# BlinkyBoard.net
KiCad netlist of a schematic drawn in EAGLE
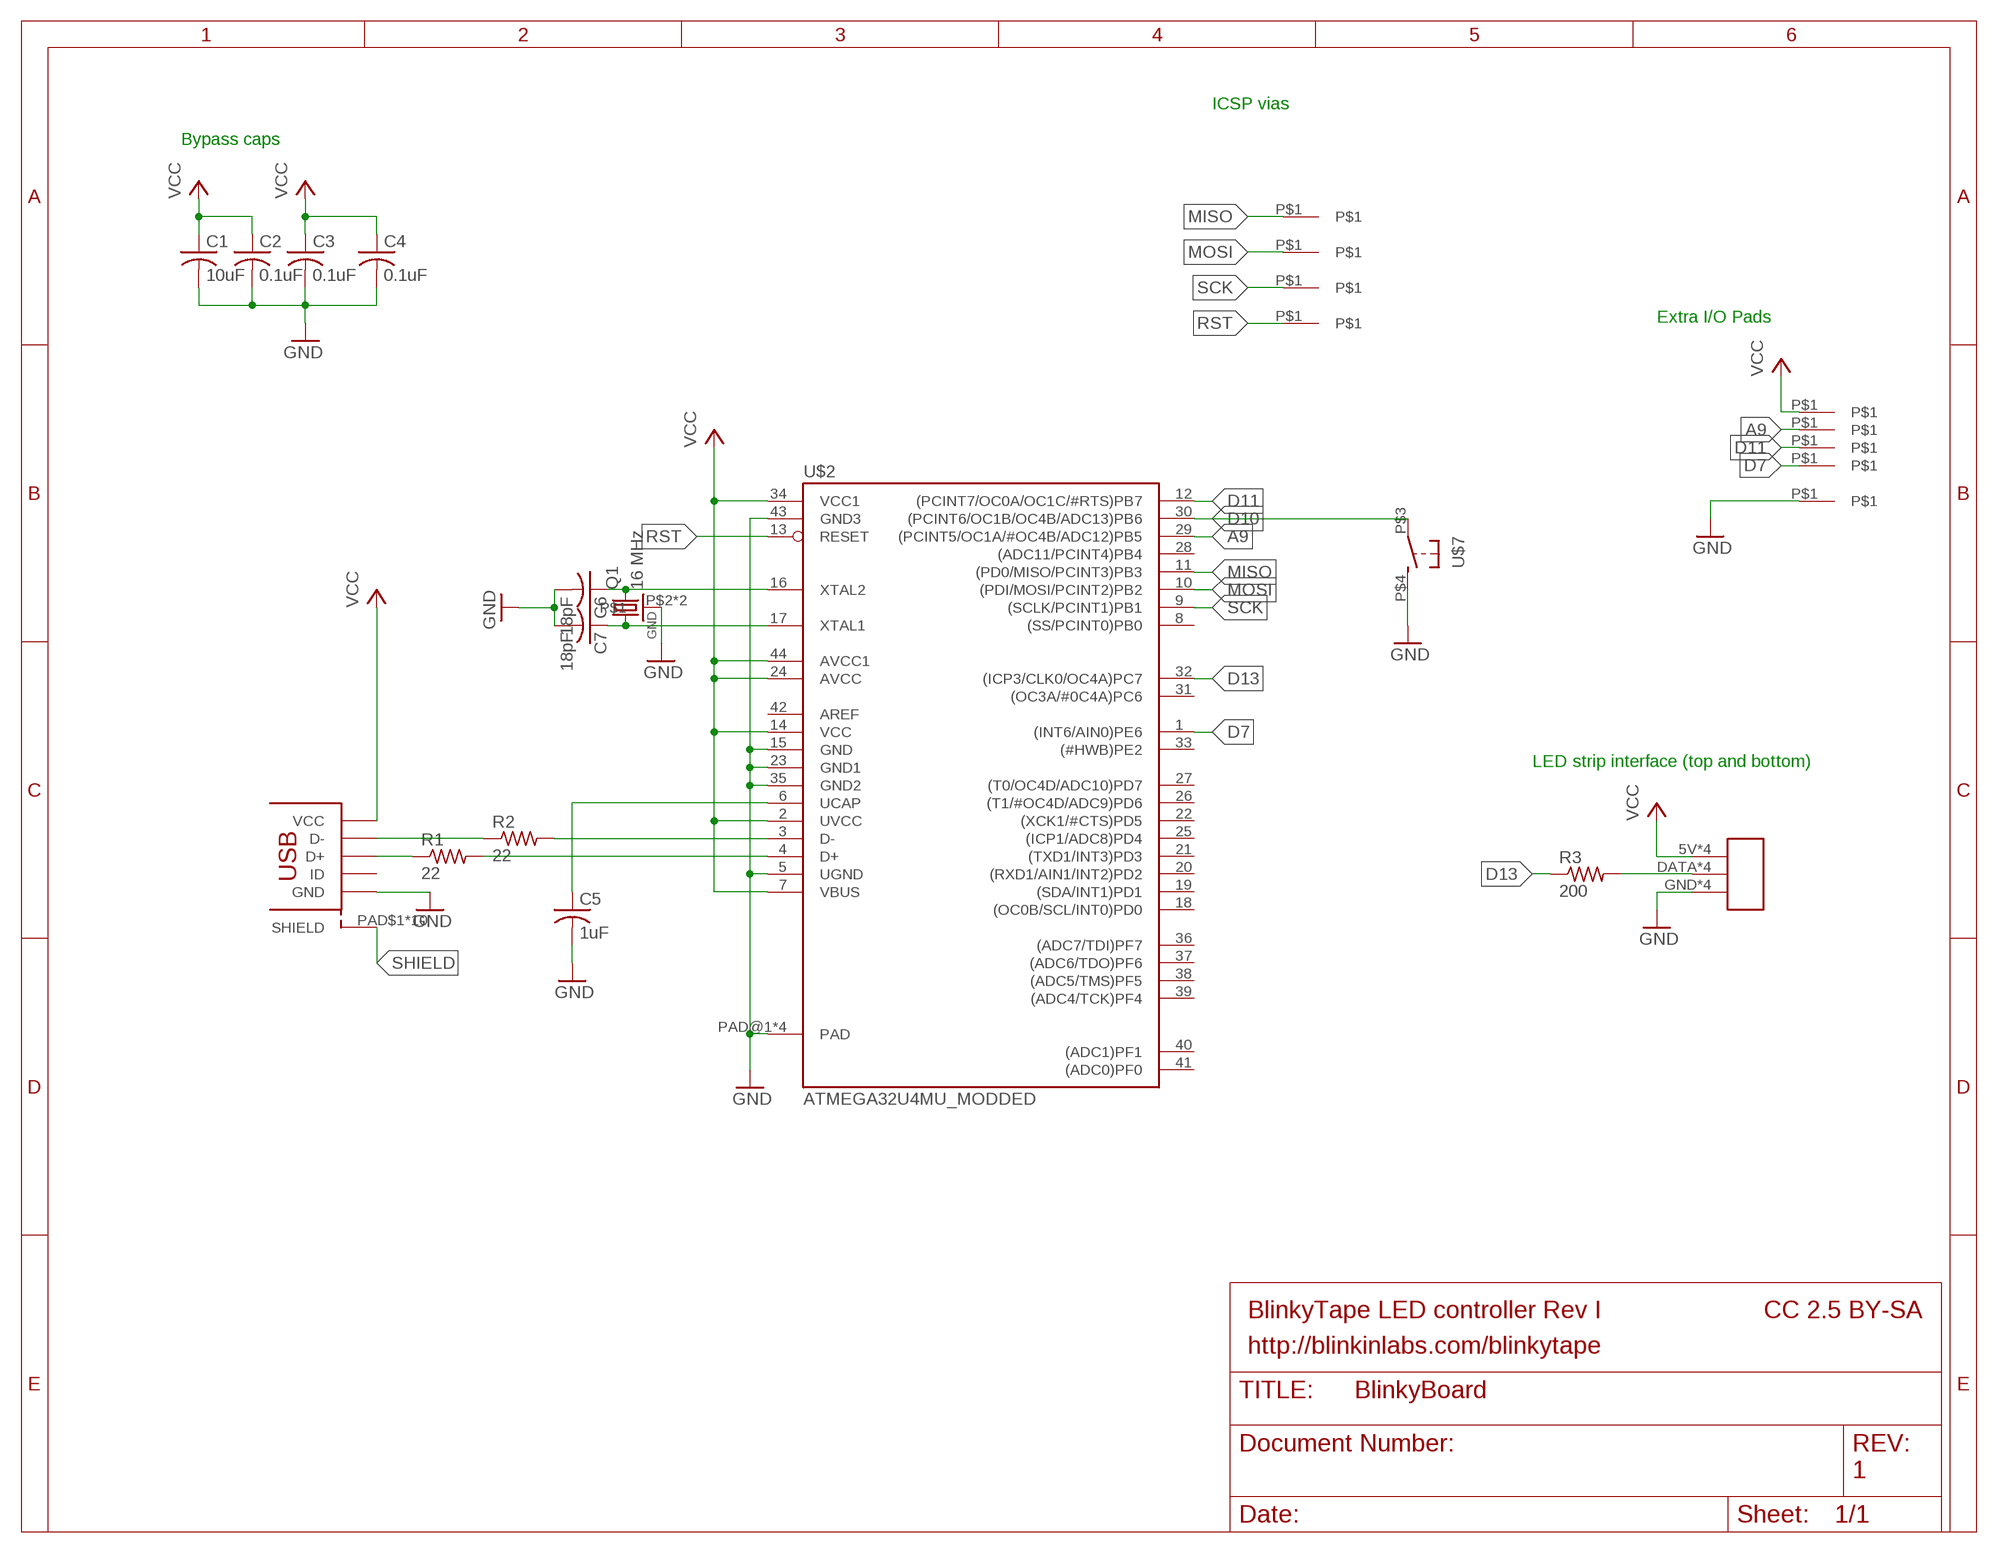
[diagram p0: schematic, sheet 1]

(export (version "E")
  (design (tool "Eeschema 10.0.6"))
  (components
    (comp (ref "C1")
      (value "10uF")
      (footprint "eagle-import:C0603K")
      (libsource (lib "eagle-import") (part "C-USC0603K"))
    )
    (comp (ref "C2")
      (value "0.1uF")
      (footprint "eagle-import:CAP_0402_KEMET_MEDIAN")
      (libsource (lib "eagle-import") (part "C_US"))
    )
    (comp (ref "C3")
      (value "0.1uF")
      (footprint "eagle-import:CAP_0402_KEMET_MEDIAN")
      (libsource (lib "eagle-import") (part "C_US"))
    )
    (comp (ref "C4")
      (value "0.1uF")
      (footprint "eagle-import:CAP_0402_KEMET_MEDIAN")
      (libsource (lib "eagle-import") (part "C_US"))
    )
    (comp (ref "C5")
      (value "1uF")
      (footprint "eagle-import:CAP_0402_KEMET_MEDIAN")
      (libsource (lib "eagle-import") (part "C_US"))
    )
    (comp (ref "C6")
      (value "18pF")
      (footprint "eagle-import:CAP_0402_KEMET_MEDIAN")
      (libsource (lib "eagle-import") (part "C_US"))
    )
    (comp (ref "C7")
      (value "18pF")
      (footprint "eagle-import:CAP_0402_KEMET_MEDIAN")
      (libsource (lib "eagle-import") (part "C_US"))
    )
    (comp (ref "Q1")
      (value "16 MHz")
      (footprint "eagle-import:CRSYTAL_2520")
      (libsource (lib "eagle-import") (part "CRYSTAL_4PAD2520"))
    )
    (comp (ref "R1")
      (value "22")
      (footprint "eagle-import:RES_0402_KEMET_MEDIAN")
      (libsource (lib "eagle-import") (part "R_US"))
    )
    (comp (ref "R2")
      (value "22")
      (footprint "eagle-import:RES_0402_KEMET_MEDIAN")
      (libsource (lib "eagle-import") (part "R_US"))
    )
    (comp (ref "R3")
      (value "200")
      (footprint "eagle-import:RES_0402_KEMET_MEDIAN")
      (libsource (lib "eagle-import") (part "R_US"))
    )
    (comp (ref "U$1")
      (value "TEST_PAD_SMT")
      (footprint "eagle-import:TEST_PAD_1MM")
      (libsource (lib "eagle-import") (part "TEST_PAD_SMT"))
    )
    (comp (ref "U$2")
      (value "ATMEGA32U4MU_MODDED")
      (footprint "eagle-import:QFN44ML_7X7_LONGLEADS_MOD")
      (libsource (lib "eagle-import") (part "ATMEGA32U4MU_MODDED"))
    )
    (comp (ref "U$3")
      (value "TEST_PAD_SMT")
      (footprint "eagle-import:TEST_PAD_1MM")
      (libsource (lib "eagle-import") (part "TEST_PAD_SMT"))
    )
    (comp (ref "U$4")
      (value "USB_MICROSMT+THRUHULE")
      (footprint "eagle-import:USB_MICRO_THRUHOLE")
      (libsource (lib "eagle-import") (part "USB_MICROSMT+THRUHULE"))
    )
    (comp (ref "U$5")
      (value "TEST_PAD_SMT")
      (footprint "eagle-import:TEST_PAD_1MM")
      (libsource (lib "eagle-import") (part "TEST_PAD_SMT"))
    )
    (comp (ref "U$6")
      (value "TEST_PAD_SMT")
      (footprint "eagle-import:TEST_PAD_1MM")
      (libsource (lib "eagle-import") (part "TEST_PAD_SMT"))
    )
    (comp (ref "U$7")
      (value "BUTTON_MOMENTARY")
      (footprint "eagle-import:BUTTON_2P_SMD")
      (libsource (lib "eagle-import") (part "BUTTON_MOMENTARY"))
    )
    (comp (ref "U$9")
      (value "WS2812B_CONNECTOR")
      (footprint "eagle-import:WS2812B_CONNECTOR")
      (libsource (lib "eagle-import") (part "WS2812B_CONNECTOR"))
    )
    (comp (ref "U$10")
      (value "TEST_PAD_SMT")
      (footprint "eagle-import:TEST_PAD_SMT")
      (libsource (lib "eagle-import") (part "blinkiverse_TEST_PAD_SMT"))
    )
    (comp (ref "U$11")
      (value "TEST_PAD_SMT")
      (footprint "eagle-import:TEST_PAD_SMT")
      (libsource (lib "eagle-import") (part "blinkiverse_TEST_PAD_SMT"))
    )
    (comp (ref "U$12")
      (value "TEST_PAD_SMT")
      (footprint "eagle-import:TEST_PAD_SMT")
      (libsource (lib "eagle-import") (part "blinkiverse_TEST_PAD_SMT"))
    )
    (comp (ref "U$13")
      (value "TEST_PAD_SMT")
      (footprint "eagle-import:TEST_PAD_SMT")
      (libsource (lib "eagle-import") (part "blinkiverse_TEST_PAD_SMT"))
    )
    (comp (ref "U$14")
      (value "TEST_PAD_SMT")
      (footprint "eagle-import:TEST_PAD_SMT")
      (libsource (lib "eagle-import") (part "blinkiverse_TEST_PAD_SMT"))
    )
  )
  (nets
    (net (code "1") (name "/AREF") (class "Default")
      (node (ref "U$2") (pin "42") (pinfunction "AREF_42") (pintype "power_in"))
    )
    (net (code "2") (name "A9") (class "Default")
      (node (ref "U$11") (pin "P$1") (pinfunction "P$1_P$1") (pintype "bidirectional"))
      (node (ref "U$2") (pin "29") (pinfunction "(PCINT5/OC1A/#OC4B/ADC12)PB5_29") (pintype "bidirectional"))
    )
    (net (code "3") (name "D7") (class "Default")
      (node (ref "U$10") (pin "P$1") (pinfunction "P$1_P$1") (pintype "bidirectional"))
      (node (ref "U$2") (pin "1") (pinfunction "(INT6/AIN0)PE6_1") (pintype "bidirectional"))
    )
    (net (code "4") (name "D10") (class "Default")
      (node (ref "U$2") (pin "30") (pinfunction "(PCINT6/OC1B/OC4B/ADC13)PB6_30") (pintype "bidirectional"))
      (node (ref "U$7") (pin "P$3") (pinfunction "P_P$3") (pintype "passive"))
    )
    (net (code "5") (name "D11") (class "Default")
      (node (ref "U$14") (pin "P$1") (pinfunction "P$1_P$1") (pintype "bidirectional"))
      (node (ref "U$2") (pin "12") (pinfunction "(PCINT7/OC0A/OC1C/#RTS)PB7_12") (pintype "bidirectional"))
    )
    (net (code "6") (name "D13") (class "Default")
      (node (ref "R3") (pin "P$1") (pinfunction "1_P$1") (pintype "passive"))
      (node (ref "U$2") (pin "32") (pinfunction "(ICP3/CLK0/OC4A)PC7_32") (pintype "bidirectional"))
    )
    (net (code "7") (name "GND") (class "Default")
      (node (ref "C1") (pin "2") (pinfunction "2_2") (pintype "passive"))
      (node (ref "C2") (pin "P$2") (pinfunction "2_P$2") (pintype "passive"))
      (node (ref "C3") (pin "P$2") (pinfunction "2_P$2") (pintype "passive"))
      (node (ref "C4") (pin "P$2") (pinfunction "2_P$2") (pintype "passive"))
      (node (ref "C5") (pin "P$2") (pinfunction "2_P$2") (pintype "passive"))
      (node (ref "C6") (pin "P$2") (pinfunction "2_P$2") (pintype "passive"))
      (node (ref "C7") (pin "P$2") (pinfunction "2_P$2") (pintype "passive"))
      (node (ref "Q1") (pin "P$2") (pinfunction "P$1_P$2") (pintype "bidirectional"))
      (node (ref "Q1") (pin "P$4") (pinfunction "P$1_P$4") (pintype "bidirectional"))
      (node (ref "U$13") (pin "P$1") (pinfunction "P$1_P$1") (pintype "bidirectional"))
      (node (ref "U$2") (pin "15") (pinfunction "GND_15") (pintype "power_in"))
      (node (ref "U$2") (pin "23") (pinfunction "GND1_23") (pintype "power_in"))
      (node (ref "U$2") (pin "35") (pinfunction "GND2_35") (pintype "power_in"))
      (node (ref "U$2") (pin "43") (pinfunction "GND3_43") (pintype "power_in"))
      (node (ref "U$2") (pin "5") (pinfunction "UGND_5") (pintype "power_in"))
      (node (ref "U$2") (pin "PAD@1") (pinfunction "PAD_PAD@1") (pintype "power_in"))
      (node (ref "U$2") (pin "PAD@13") (pinfunction "PAD_PAD@13") (pintype "power_in"))
      (node (ref "U$2") (pin "PAD@16") (pinfunction "PAD_PAD@16") (pintype "power_in"))
      (node (ref "U$2") (pin "PAD@4") (pinfunction "PAD_PAD@4") (pintype "power_in"))
      (node (ref "U$4") (pin "PIN$5") (pinfunction "GND_PIN$5") (pintype "bidirectional"))
      (node (ref "U$7") (pin "P$4") (pinfunction "S_P$4") (pintype "passive"))
      (node (ref "U$9") (pin "GND") (pinfunction "GND_GND") (pintype "bidirectional"))
      (node (ref "U$9") (pin "GND1") (pinfunction "GND_GND1") (pintype "bidirectional"))
      (node (ref "U$9") (pin "GND_1") (pinfunction "GND_GND_1") (pintype "bidirectional"))
      (node (ref "U$9") (pin "GND_2") (pinfunction "GND_GND_2") (pintype "bidirectional"))
    )
    (net (code "8") (name "MISO") (class "Default")
      (node (ref "U$1") (pin "P$1") (pinfunction "P$1_P$1") (pintype "bidirectional"))
      (node (ref "U$2") (pin "11") (pinfunction "(PD0/MISO/PCINT3)PB3_11") (pintype "bidirectional"))
    )
    (net (code "9") (name "MOSI") (class "Default")
      (node (ref "U$2") (pin "10") (pinfunction "(PDI/MOSI/PCINT2)PB2_10") (pintype "bidirectional"))
      (node (ref "U$3") (pin "P$1") (pinfunction "P$1_P$1") (pintype "bidirectional"))
    )
    (net (code "10") (name "Net-(C5-1)") (class "Default")
      (node (ref "C5") (pin "P$1") (pinfunction "1_P$1") (pintype "passive"))
      (node (ref "U$2") (pin "6") (pinfunction "UCAP_6") (pintype "passive"))
    )
    (net (code "11") (name "Net-(C6-1)") (class "Default")
      (node (ref "C6") (pin "P$1") (pinfunction "1_P$1") (pintype "passive"))
      (node (ref "Q1") (pin "P$3") (pinfunction "2_P$3") (pintype "passive"))
      (node (ref "U$2") (pin "16") (pinfunction "XTAL2_16") (pintype "bidirectional"))
    )
    (net (code "12") (name "Net-(C7-1)") (class "Default")
      (node (ref "C7") (pin "P$1") (pinfunction "1_P$1") (pintype "passive"))
      (node (ref "Q1") (pin "P$1") (pinfunction "1_P$1") (pintype "passive"))
      (node (ref "U$2") (pin "17") (pinfunction "XTAL1_17") (pintype "bidirectional"))
    )
    (net (code "13") (name "Net-(R1-1)") (class "Default")
      (node (ref "R1") (pin "P$1") (pinfunction "1_P$1") (pintype "passive"))
      (node (ref "U$4") (pin "PIN$3") (pinfunction "D+_PIN$3") (pintype "bidirectional"))
    )
    (net (code "14") (name "Net-(R1-2)") (class "Default")
      (node (ref "R1") (pin "P$2") (pinfunction "2_P$2") (pintype "passive"))
      (node (ref "U$2") (pin "4") (pinfunction "D+_4") (pintype "bidirectional"))
    )
    (net (code "15") (name "Net-(R2-1)") (class "Default")
      (node (ref "R2") (pin "P$1") (pinfunction "1_P$1") (pintype "passive"))
      (node (ref "U$4") (pin "PIN$2") (pinfunction "D-_PIN$2") (pintype "bidirectional"))
    )
    (net (code "16") (name "Net-(R2-2)") (class "Default")
      (node (ref "R2") (pin "P$2") (pinfunction "2_P$2") (pintype "passive"))
      (node (ref "U$2") (pin "3") (pinfunction "D-_3") (pintype "bidirectional"))
    )
    (net (code "17") (name "Net-(R3-2)") (class "Default")
      (node (ref "R3") (pin "P$2") (pinfunction "2_P$2") (pintype "passive"))
      (node (ref "U$9") (pin "DATA") (pinfunction "DATA_DATA") (pintype "bidirectional"))
      (node (ref "U$9") (pin "DATA1") (pinfunction "DATA_DATA1") (pintype "bidirectional"))
      (node (ref "U$9") (pin "DATA_1") (pinfunction "DATA_DATA_1") (pintype "bidirectional"))
      (node (ref "U$9") (pin "DATA_2") (pinfunction "DATA_DATA_2") (pintype "bidirectional"))
    )
    (net (code "18") (name "RST") (class "Default")
      (node (ref "U$2") (pin "13") (pinfunction "RESET_13") (pintype "input"))
      (node (ref "U$6") (pin "P$1") (pinfunction "P$1_P$1") (pintype "bidirectional"))
    )
    (net (code "19") (name "SCK") (class "Default")
      (node (ref "U$2") (pin "9") (pinfunction "(SCLK/PCINT1)PB1_9") (pintype "bidirectional"))
      (node (ref "U$5") (pin "P$1") (pinfunction "P$1_P$1") (pintype "bidirectional"))
    )
    (net (code "20") (name "SHIELD") (class "Default")
      (node (ref "U$4") (pin "PAD$1") (pinfunction "SHIELD_PAD$1") (pintype "bidirectional"))
      (node (ref "U$4") (pin "PAD$10") (pinfunction "SHIELD_PAD$10") (pintype "bidirectional"))
      (node (ref "U$4") (pin "PAD$2") (pinfunction "SHIELD_PAD$2") (pintype "bidirectional"))
      (node (ref "U$4") (pin "PAD$3") (pinfunction "SHIELD_PAD$3") (pintype "bidirectional"))
      (node (ref "U$4") (pin "PAD$4") (pinfunction "SHIELD_PAD$4") (pintype "bidirectional"))
      (node (ref "U$4") (pin "PAD$5") (pinfunction "SHIELD_PAD$5") (pintype "bidirectional"))
      (node (ref "U$4") (pin "PAD$6") (pinfunction "SHIELD_PAD$6") (pintype "bidirectional"))
      (node (ref "U$4") (pin "PAD$7") (pinfunction "SHIELD_PAD$7") (pintype "bidirectional"))
      (node (ref "U$4") (pin "PAD$8") (pinfunction "SHIELD_PAD$8") (pintype "bidirectional"))
      (node (ref "U$4") (pin "PAD$9") (pinfunction "SHIELD_PAD$9") (pintype "bidirectional"))
    )
    (net (code "21") (name "VCC") (class "Default")
      (node (ref "C1") (pin "1") (pinfunction "1_1") (pintype "passive"))
      (node (ref "C2") (pin "P$1") (pinfunction "1_P$1") (pintype "passive"))
      (node (ref "C3") (pin "P$1") (pinfunction "1_P$1") (pintype "passive"))
      (node (ref "C4") (pin "P$1") (pinfunction "1_P$1") (pintype "passive"))
      (node (ref "U$12") (pin "P$1") (pinfunction "P$1_P$1") (pintype "bidirectional"))
      (node (ref "U$2") (pin "14") (pinfunction "VCC_14") (pintype "power_in"))
      (node (ref "U$2") (pin "2") (pinfunction "UVCC_2") (pintype "power_in"))
      (node (ref "U$2") (pin "24") (pinfunction "AVCC_24") (pintype "power_in"))
      (node (ref "U$2") (pin "34") (pinfunction "VCC1_34") (pintype "power_in"))
      (node (ref "U$2") (pin "44") (pinfunction "AVCC1_44") (pintype "power_in"))
      (node (ref "U$2") (pin "7") (pinfunction "VBUS_7") (pintype "input"))
      (node (ref "U$4") (pin "PIN$1") (pinfunction "VCC_PIN$1") (pintype "bidirectional"))
      (node (ref "U$9") (pin "5V") (pinfunction "5V_5V") (pintype "bidirectional"))
      (node (ref "U$9") (pin "5V1") (pinfunction "5V_5V1") (pintype "bidirectional"))
      (node (ref "U$9") (pin "5V_1") (pinfunction "5V_5V_1") (pintype "bidirectional"))
      (node (ref "U$9") (pin "5V_2") (pinfunction "5V_5V_2") (pintype "bidirectional"))
    )
    (net (code "22") (name "unconnected-(U$2-(#HWB)PE2-Pad33)") (class "Default")
      (node (ref "U$2") (pin "33") (pinfunction "(#HWB)PE2_33") (pintype "bidirectional"))
    )
    (net (code "23") (name "unconnected-(U$2-(ADC0)PF0-Pad41)") (class "Default")
      (node (ref "U$2") (pin "41") (pinfunction "(ADC0)PF0_41") (pintype "bidirectional"))
    )
    (net (code "24") (name "unconnected-(U$2-(ADC1)PF1-Pad40)") (class "Default")
      (node (ref "U$2") (pin "40") (pinfunction "(ADC1)PF1_40") (pintype "bidirectional"))
    )
    (net (code "25") (name "unconnected-(U$2-(ADC4{slash}TCK)PF4-Pad39)") (class "Default")
      (node (ref "U$2") (pin "39") (pinfunction "(ADC4/TCK)PF4_39") (pintype "bidirectional"))
    )
    (net (code "26") (name "unconnected-(U$2-(ADC5{slash}TMS)PF5-Pad38)") (class "Default")
      (node (ref "U$2") (pin "38") (pinfunction "(ADC5/TMS)PF5_38") (pintype "bidirectional"))
    )
    (net (code "27") (name "unconnected-(U$2-(ADC6{slash}TDO)PF6-Pad37)") (class "Default")
      (node (ref "U$2") (pin "37") (pinfunction "(ADC6/TDO)PF6_37") (pintype "bidirectional"))
    )
    (net (code "28") (name "unconnected-(U$2-(ADC7{slash}TDI)PF7-Pad36)") (class "Default")
      (node (ref "U$2") (pin "36") (pinfunction "(ADC7/TDI)PF7_36") (pintype "bidirectional"))
    )
    (net (code "29") (name "unconnected-(U$2-(ADC11{slash}PCINT4)PB4-Pad28)") (class "Default")
      (node (ref "U$2") (pin "28") (pinfunction "(ADC11/PCINT4)PB4_28") (pintype "bidirectional"))
    )
    (net (code "30") (name "unconnected-(U$2-(ICP1{slash}ADC8)PD4-Pad25)") (class "Default")
      (node (ref "U$2") (pin "25") (pinfunction "(ICP1/ADC8)PD4_25") (pintype "bidirectional"))
    )
    (net (code "31") (name "unconnected-(U$2-(OC0B{slash}SCL{slash}INT0)PD0-Pad18)") (class "Default")
      (node (ref "U$2") (pin "18") (pinfunction "(OC0B/SCL/INT0)PD0_18") (pintype "bidirectional"))
    )
    (net (code "32") (name "unconnected-(U$2-(OC3A{slash}#0C4A)PC6-Pad31)") (class "Default")
      (node (ref "U$2") (pin "31") (pinfunction "(OC3A/#0C4A)PC6_31") (pintype "bidirectional"))
    )
    (net (code "33") (name "unconnected-(U$2-(RXD1{slash}AIN1{slash}INT2)PD2-Pad20)") (class "Default")
      (node (ref "U$2") (pin "20") (pinfunction "(RXD1/AIN1/INT2)PD2_20") (pintype "bidirectional"))
    )
    (net (code "34") (name "unconnected-(U$2-(SDA{slash}INT1)PD1-Pad19)") (class "Default")
      (node (ref "U$2") (pin "19") (pinfunction "(SDA/INT1)PD1_19") (pintype "bidirectional"))
    )
    (net (code "35") (name "unconnected-(U$2-(SS{slash}PCINT0)PB0-Pad8)") (class "Default")
      (node (ref "U$2") (pin "8") (pinfunction "(SS/PCINT0)PB0_8") (pintype "bidirectional"))
    )
    (net (code "36") (name "unconnected-(U$2-(T0{slash}OC4D{slash}ADC10)PD7-Pad27)") (class "Default")
      (node (ref "U$2") (pin "27") (pinfunction "(T0/OC4D/ADC10)PD7_27") (pintype "bidirectional"))
    )
    (net (code "37") (name "unconnected-(U$2-(T1{slash}#OC4D{slash}ADC9)PD6-Pad26)") (class "Default")
      (node (ref "U$2") (pin "26") (pinfunction "(T1/#OC4D/ADC9)PD6_26") (pintype "bidirectional"))
    )
    (net (code "38") (name "unconnected-(U$2-(TXD1{slash}INT3)PD3-Pad21)") (class "Default")
      (node (ref "U$2") (pin "21") (pinfunction "(TXD1/INT3)PD3_21") (pintype "bidirectional"))
    )
    (net (code "39") (name "unconnected-(U$2-(XCK1{slash}#CTS)PD5-Pad22)") (class "Default")
      (node (ref "U$2") (pin "22") (pinfunction "(XCK1/#CTS)PD5_22") (pintype "bidirectional"))
    )
    (net (code "40") (name "unconnected-(U$4-ID-PadPIN$4)") (class "Default")
      (node (ref "U$4") (pin "PIN$4") (pinfunction "ID_PIN$4") (pintype "bidirectional"))
    )
  )
)
